# AQETHBluePill_w_RESET.net
KiCad netlist of a schematic drawn in EAGLE
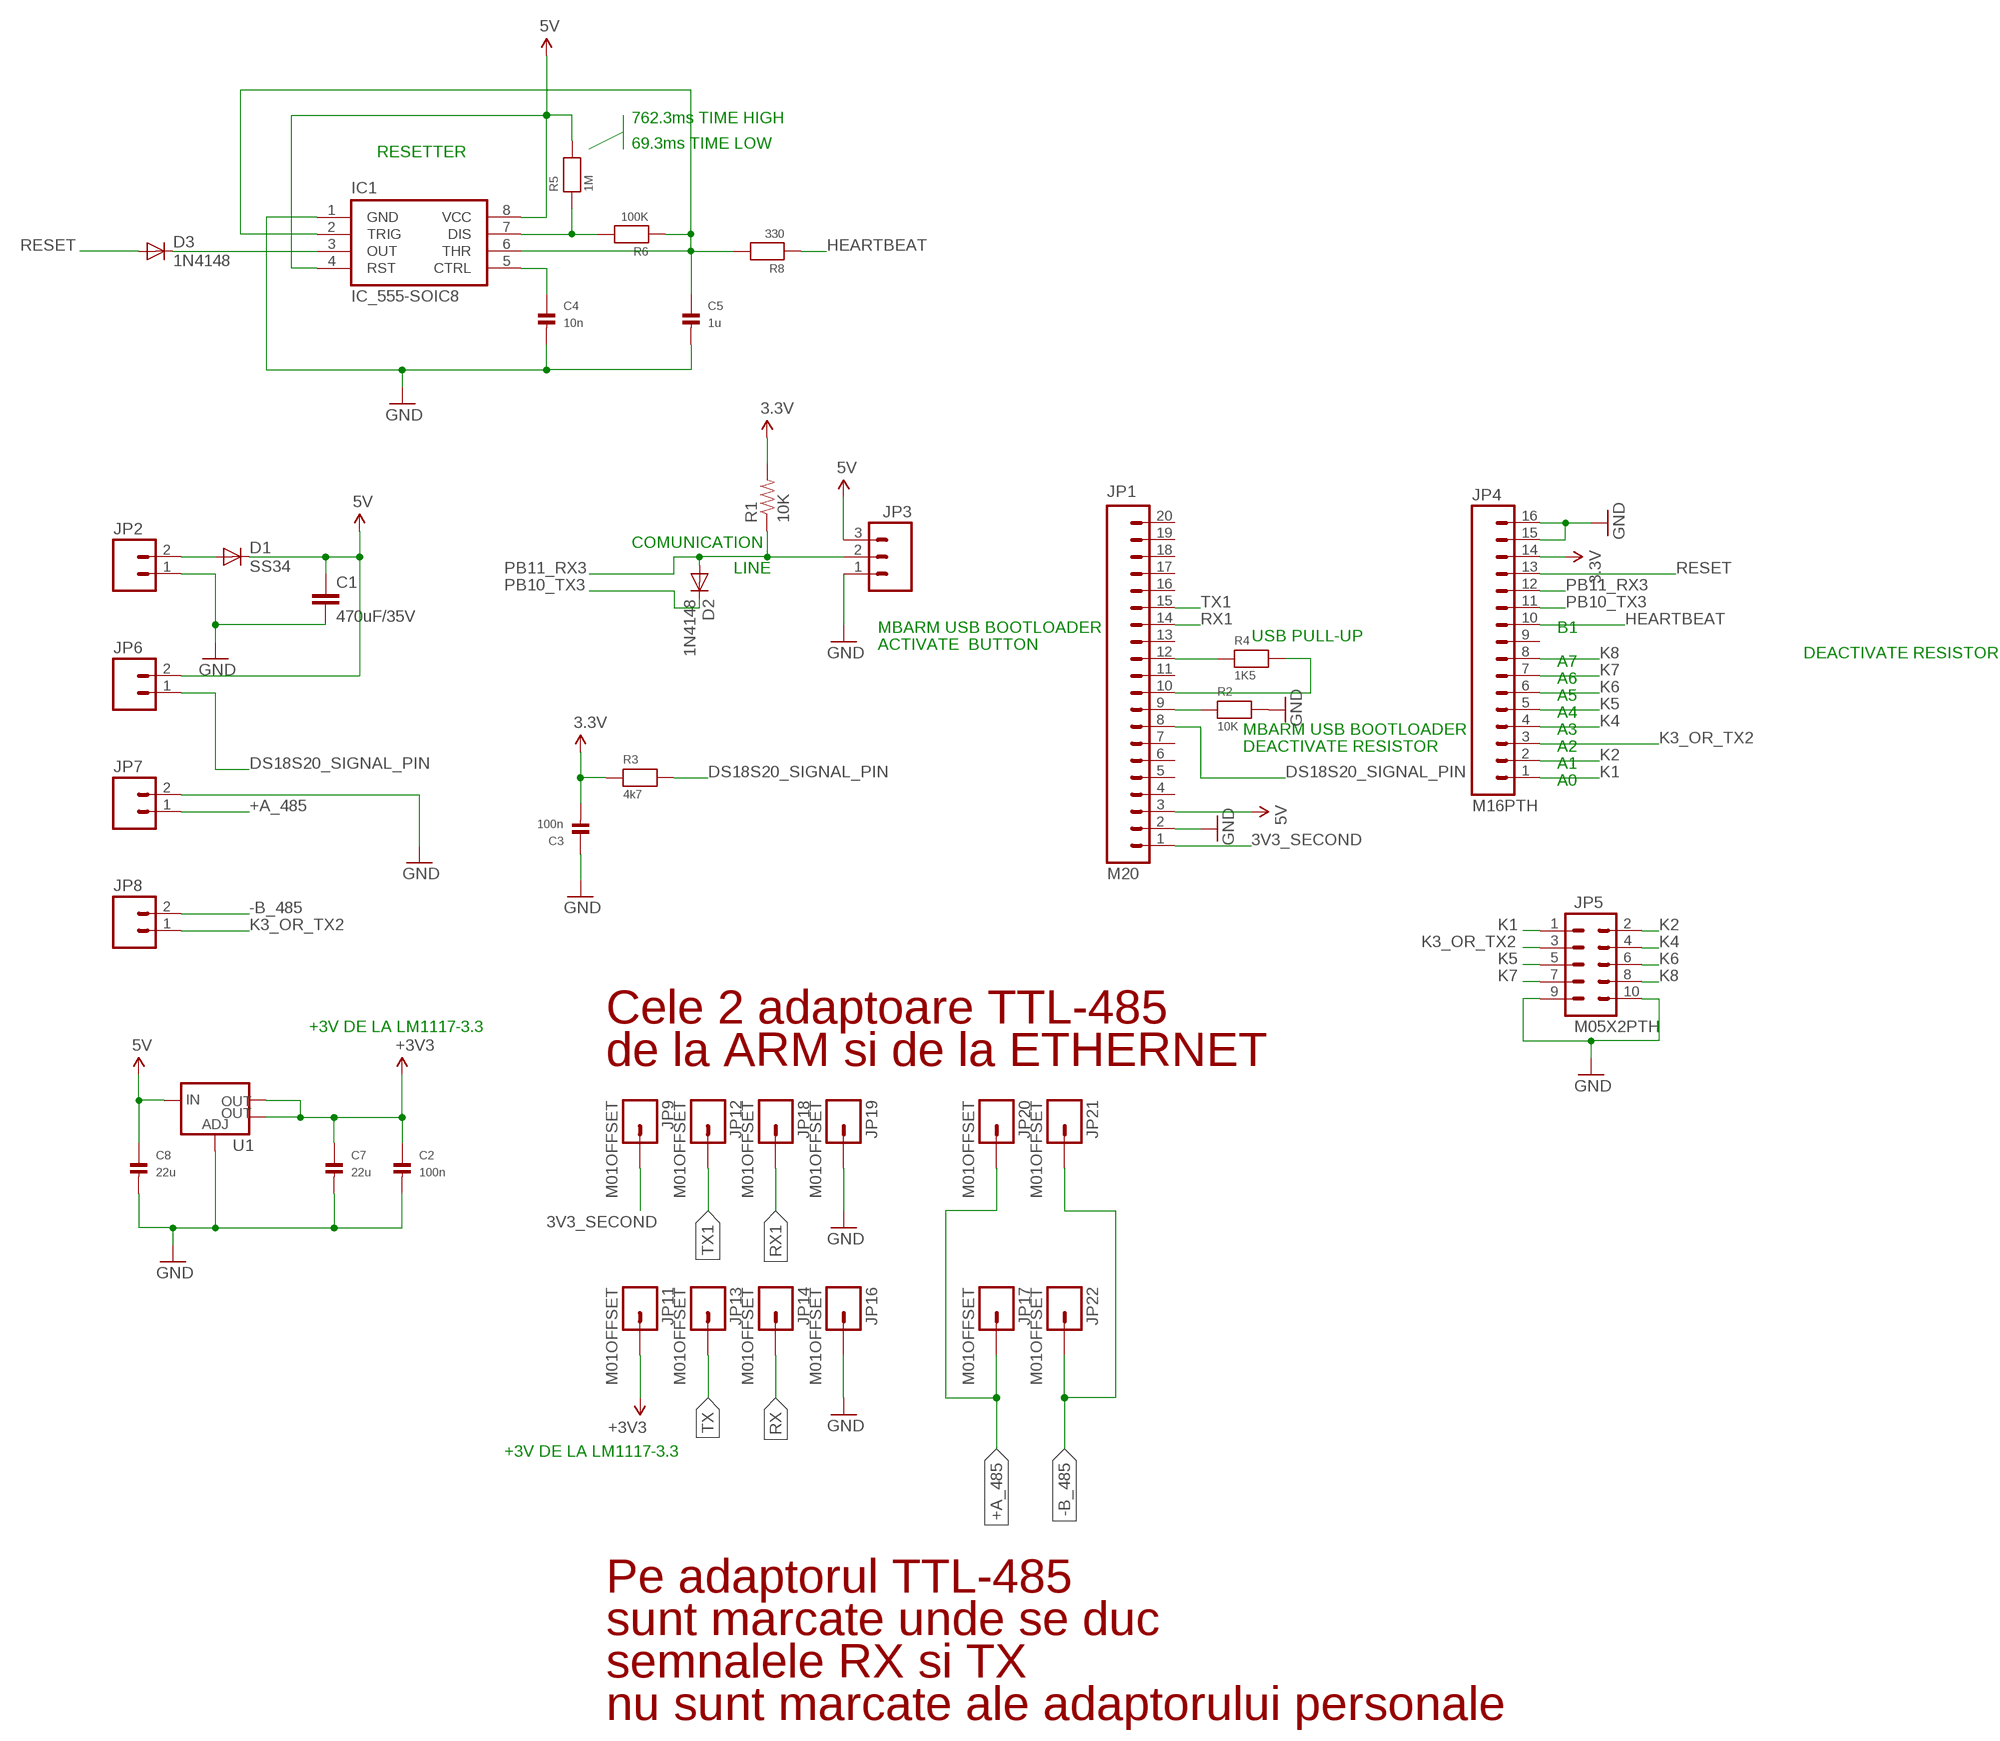
[diagram p0: schematic, sheet 1]

(export (version "E")
  (design (tool "Eeschema 10.0.6"))
  (components
    (comp (ref "C1")
      (value "470uF/35V")
      (footprint "eagle-import:CAP-PTH-5MM")
      (libsource (lib "eagle-import") (part "CAPPTH1"))
    )
    (comp (ref "C2")
      (value "100n")
      (footprint "eagle-import:_0805MP")
      (libsource (lib "eagle-import") (part "CAP_CERAMIC_0805MP"))
    )
    (comp (ref "C3")
      (value "100n")
      (footprint "eagle-import:_0805MP")
      (libsource (lib "eagle-import") (part "CAP_CERAMIC_0805MP"))
    )
    (comp (ref "C4")
      (value "10n")
      (footprint "eagle-import:_0805MP")
      (libsource (lib "eagle-import") (part "CAP_CERAMIC_0805MP"))
    )
    (comp (ref "C5")
      (value "1u")
      (footprint "eagle-import:1206")
      (libsource (lib "eagle-import") (part "CAP_CERAMIC1206"))
    )
    (comp (ref "C7")
      (value "22u")
      (footprint "eagle-import:1206")
      (libsource (lib "eagle-import") (part "CAP_CERAMIC1206"))
    )
    (comp (ref "C8")
      (value "22u")
      (footprint "eagle-import:1206")
      (libsource (lib "eagle-import") (part "CAP_CERAMIC1206"))
    )
    (comp (ref "D1")
      (value "SS34")
      (footprint "eagle-import:SMC")
      (libsource (lib "eagle-import") (part "DIODE-SMC"))
    )
    (comp (ref "D2")
      (value "1N4148")
      (footprint "eagle-import:MINIMELF")
      (libsource (lib "eagle-import") (part "DIODE-MINIMELF"))
    )
    (comp (ref "D3")
      (value "1N4148")
      (footprint "eagle-import:MINIMELF")
      (libsource (lib "eagle-import") (part "DIODE-MINIMELF"))
    )
    (comp (ref "IC1")
      (value "IC_555-SOIC8")
      (footprint "eagle-import:SOIC-8")
      (libsource (lib "eagle-import") (part "IC_555-SOIC8"))
    )
    (comp (ref "JP1")
      (value "M20")
      (footprint "eagle-import:1X20")
      (libsource (lib "eagle-import") (part "M20"))
    )
    (comp (ref "JP2")
      (value "M025MM")
      (footprint "eagle-import:SCREWTERMINAL-5MM-2")
      (libsource (lib "eagle-import") (part "M025MM"))
    )
    (comp (ref "JP3")
      (value "M03LOCK_LONGPADS")
      (footprint "eagle-import:1X03_LOCK_LONGPADS")
      (libsource (lib "eagle-import") (part "M03LOCK_LONGPADS"))
    )
    (comp (ref "JP4")
      (value "M16PTH")
      (footprint "eagle-import:1X16")
      (libsource (lib "eagle-import") (part "M16PTH"))
    )
    (comp (ref "JP5")
      (value "M05X2PTH")
      (footprint "eagle-import:AVR_ICSP")
      (libsource (lib "eagle-import") (part "M05X2PTH"))
    )
    (comp (ref "JP6")
      (value "M025MM")
      (footprint "eagle-import:SCREWTERMINAL-5MM-2")
      (libsource (lib "eagle-import") (part "M025MM"))
    )
    (comp (ref "JP7")
      (value "M025MM")
      (footprint "eagle-import:SCREWTERMINAL-5MM-2")
      (libsource (lib "eagle-import") (part "M025MM"))
    )
    (comp (ref "JP8")
      (value "M025MM")
      (footprint "eagle-import:SCREWTERMINAL-5MM-2")
      (libsource (lib "eagle-import") (part "M025MM"))
    )
    (comp (ref "JP9")
      (value "M01OFFSET")
      (footprint "eagle-import:1X01_OFFSET")
      (libsource (lib "eagle-import") (part "M01OFFSET"))
    )
    (comp (ref "JP11")
      (value "M01OFFSET")
      (footprint "eagle-import:1X01_OFFSET")
      (libsource (lib "eagle-import") (part "M01OFFSET"))
    )
    (comp (ref "JP12")
      (value "M01OFFSET")
      (footprint "eagle-import:1X01_OFFSET")
      (libsource (lib "eagle-import") (part "M01OFFSET"))
    )
    (comp (ref "JP13")
      (value "M01OFFSET")
      (footprint "eagle-import:1X01_OFFSET")
      (libsource (lib "eagle-import") (part "M01OFFSET"))
    )
    (comp (ref "JP14")
      (value "M01OFFSET")
      (footprint "eagle-import:1X01_OFFSET")
      (libsource (lib "eagle-import") (part "M01OFFSET"))
    )
    (comp (ref "JP16")
      (value "M01OFFSET")
      (footprint "eagle-import:1X01_OFFSET")
      (libsource (lib "eagle-import") (part "M01OFFSET"))
    )
    (comp (ref "JP17")
      (value "M01OFFSET")
      (footprint "eagle-import:1X01_OFFSET")
      (libsource (lib "eagle-import") (part "M01OFFSET"))
    )
    (comp (ref "JP18")
      (value "M01OFFSET")
      (footprint "eagle-import:1X01_OFFSET")
      (libsource (lib "eagle-import") (part "M01OFFSET"))
    )
    (comp (ref "JP19")
      (value "M01OFFSET")
      (footprint "eagle-import:1X01_OFFSET")
      (libsource (lib "eagle-import") (part "M01OFFSET"))
    )
    (comp (ref "JP20")
      (value "M01OFFSET")
      (footprint "eagle-import:1X01_OFFSET")
      (libsource (lib "eagle-import") (part "M01OFFSET"))
    )
    (comp (ref "JP21")
      (value "M01OFFSET")
      (footprint "eagle-import:1X01_OFFSET")
      (libsource (lib "eagle-import") (part "M01OFFSET"))
    )
    (comp (ref "JP22")
      (value "M01OFFSET")
      (footprint "eagle-import:1X01_OFFSET")
      (libsource (lib "eagle-import") (part "M01OFFSET"))
    )
    (comp (ref "R1")
      (value "10K")
      (footprint "eagle-import:1206")
      (libsource (lib "eagle-import") (part "RESISTOR1206"))
    )
    (comp (ref "R2")
      (value "10K")
      (footprint "eagle-import:_0805MP")
      (libsource (lib "eagle-import") (part "RESISTOR_0805MP"))
    )
    (comp (ref "R3")
      (value "4k7")
      (footprint "eagle-import:_0805MP")
      (libsource (lib "eagle-import") (part "RESISTOR_0805MP"))
    )
    (comp (ref "R4")
      (value "1K5")
      (footprint "eagle-import:_0805MP")
      (libsource (lib "eagle-import") (part "RESISTOR_0805MP"))
    )
    (comp (ref "R5")
      (value "1M")
      (footprint "eagle-import:_0805MP")
      (libsource (lib "eagle-import") (part "RESISTOR_0805MP"))
    )
    (comp (ref "R6")
      (value "100K")
      (footprint "eagle-import:_0805MP")
      (libsource (lib "eagle-import") (part "RESISTOR_0805MP"))
    )
    (comp (ref "R8")
      (value "330")
      (footprint "eagle-import:_0805MP")
      (libsource (lib "eagle-import") (part "RESISTOR_0805MP"))
    )
    (comp (ref "U1")
      (value "V_REG_LM1117SOT223")
      (footprint "eagle-import:SOT223")
      (libsource (lib "eagle-import") (part "V_REG_LM1117SOT223"))
    )
  )
  (nets
    (net (code "1") (name "+3V3") (class "Default")
      (node (ref "C2") (pin "1") (pinfunction "P$1_1") (pintype "passive"))
      (node (ref "C7") (pin "1") (pinfunction "P$1_1") (pintype "passive"))
      (node (ref "JP11") (pin "1") (pinfunction "1_1") (pintype "passive"))
      (node (ref "U1") (pin "2") (pinfunction "OUT_2") (pintype "output"))
      (node (ref "U1") (pin "4") (pinfunction "OUT_4") (pintype "output"))
    )
    (net (code "2") (name "+A_485") (class "Default")
      (node (ref "JP17") (pin "1") (pinfunction "1_1") (pintype "passive"))
      (node (ref "JP20") (pin "1") (pinfunction "1_1") (pintype "passive"))
      (node (ref "JP7") (pin "1") (pinfunction "1_1") (pintype "passive"))
    )
    (net (code "3") (name "-B_485") (class "Default")
      (node (ref "JP21") (pin "1") (pinfunction "1_1") (pintype "passive"))
      (node (ref "JP22") (pin "1") (pinfunction "1_1") (pintype "passive"))
      (node (ref "JP8") (pin "2") (pinfunction "2_2") (pintype "passive"))
    )
    (net (code "4") (name "/3V3_SECOND") (class "Default")
      (node (ref "JP1") (pin "1") (pinfunction "1_1") (pintype "passive"))
      (node (ref "JP9") (pin "1") (pinfunction "1_1") (pintype "passive"))
    )
    (net (code "5") (name "/DS18S20_SIGNAL_PIN") (class "Default")
      (node (ref "JP1") (pin "8") (pinfunction "8_8") (pintype "passive"))
      (node (ref "JP6") (pin "1") (pinfunction "1_1") (pintype "passive"))
      (node (ref "R3") (pin "2") (pinfunction "2_2") (pintype "passive"))
    )
    (net (code "6") (name "/HEARTBEAT") (class "Default")
      (node (ref "JP4") (pin "10") (pinfunction "10_10") (pintype "passive"))
      (node (ref "R8") (pin "1") (pinfunction "1_1") (pintype "passive"))
    )
    (net (code "7") (name "/K1") (class "Default")
      (node (ref "JP4") (pin "1") (pinfunction "1_1") (pintype "passive"))
      (node (ref "JP5") (pin "1") (pinfunction "1_1") (pintype "passive"))
    )
    (net (code "8") (name "/K2") (class "Default")
      (node (ref "JP4") (pin "2") (pinfunction "2_2") (pintype "passive"))
      (node (ref "JP5") (pin "2") (pinfunction "2_2") (pintype "passive"))
    )
    (net (code "9") (name "/K3_OR_TX2") (class "Default")
      (node (ref "JP4") (pin "3") (pinfunction "3_3") (pintype "passive"))
      (node (ref "JP5") (pin "3") (pinfunction "3_3") (pintype "passive"))
      (node (ref "JP8") (pin "1") (pinfunction "1_1") (pintype "passive"))
    )
    (net (code "10") (name "/K4") (class "Default")
      (node (ref "JP4") (pin "4") (pinfunction "4_4") (pintype "passive"))
      (node (ref "JP5") (pin "4") (pinfunction "4_4") (pintype "passive"))
    )
    (net (code "11") (name "/K5") (class "Default")
      (node (ref "JP4") (pin "5") (pinfunction "5_5") (pintype "passive"))
      (node (ref "JP5") (pin "5") (pinfunction "5_5") (pintype "passive"))
    )
    (net (code "12") (name "/K6") (class "Default")
      (node (ref "JP4") (pin "6") (pinfunction "6_6") (pintype "passive"))
      (node (ref "JP5") (pin "6") (pinfunction "6_6") (pintype "passive"))
    )
    (net (code "13") (name "/K7") (class "Default")
      (node (ref "JP4") (pin "7") (pinfunction "7_7") (pintype "passive"))
      (node (ref "JP5") (pin "7") (pinfunction "7_7") (pintype "passive"))
    )
    (net (code "14") (name "/K8") (class "Default")
      (node (ref "JP4") (pin "8") (pinfunction "8_8") (pintype "passive"))
      (node (ref "JP5") (pin "8") (pinfunction "8_8") (pintype "passive"))
    )
    (net (code "15") (name "/PB10_TX3") (class "Default")
      (node (ref "D2") (pin "C") (pinfunction "C_C") (pintype "passive"))
      (node (ref "JP4") (pin "11") (pinfunction "11_11") (pintype "passive"))
    )
    (net (code "16") (name "/PB11_RX3") (class "Default")
      (node (ref "D2") (pin "A") (pinfunction "A_A") (pintype "passive"))
      (node (ref "JP3") (pin "2") (pinfunction "2_2") (pintype "passive"))
      (node (ref "JP4") (pin "12") (pinfunction "12_12") (pintype "passive"))
      (node (ref "R1") (pin "1") (pinfunction "1_1") (pintype "passive"))
    )
    (net (code "17") (name "/RESET") (class "Default")
      (node (ref "D3") (pin "A") (pinfunction "A_A") (pintype "passive"))
      (node (ref "JP4") (pin "13") (pinfunction "13_13") (pintype "passive"))
    )
    (net (code "18") (name "3.3V") (class "Default")
      (node (ref "C3") (pin "2") (pinfunction "P$2_2") (pintype "passive"))
      (node (ref "JP4") (pin "14") (pinfunction "14_14") (pintype "passive"))
      (node (ref "R1") (pin "2") (pinfunction "2_2") (pintype "passive"))
      (node (ref "R3") (pin "1") (pinfunction "1_1") (pintype "passive"))
    )
    (net (code "19") (name "5V") (class "Default")
      (node (ref "C1") (pin "1") (pinfunction "1_1") (pintype "passive"))
      (node (ref "C8") (pin "1") (pinfunction "P$1_1") (pintype "passive"))
      (node (ref "D1") (pin "C") (pinfunction "C_C") (pintype "passive"))
      (node (ref "IC1") (pin "4") (pinfunction "RST_4") (pintype "input"))
      (node (ref "IC1") (pin "8") (pinfunction "VCC_8") (pintype "power_in"))
      (node (ref "JP1") (pin "3") (pinfunction "3_3") (pintype "passive"))
      (node (ref "JP3") (pin "3") (pinfunction "3_3") (pintype "passive"))
      (node (ref "JP6") (pin "2") (pinfunction "2_2") (pintype "passive"))
      (node (ref "R5") (pin "2") (pinfunction "2_2") (pintype "passive"))
      (node (ref "U1") (pin "3") (pinfunction "IN_3") (pintype "input"))
    )
    (net (code "20") (name "GND") (class "Default")
      (node (ref "C1") (pin "2") (pinfunction "2_2") (pintype "passive"))
      (node (ref "C2") (pin "2") (pinfunction "P$2_2") (pintype "passive"))
      (node (ref "C3") (pin "1") (pinfunction "P$1_1") (pintype "passive"))
      (node (ref "C4") (pin "2") (pinfunction "P$2_2") (pintype "passive"))
      (node (ref "C5") (pin "2") (pinfunction "P$2_2") (pintype "passive"))
      (node (ref "C7") (pin "2") (pinfunction "P$2_2") (pintype "passive"))
      (node (ref "C8") (pin "2") (pinfunction "P$2_2") (pintype "passive"))
      (node (ref "IC1") (pin "1") (pinfunction "GND_1") (pintype "power_in"))
      (node (ref "JP1") (pin "2") (pinfunction "2_2") (pintype "passive"))
      (node (ref "JP16") (pin "1") (pinfunction "1_1") (pintype "passive"))
      (node (ref "JP19") (pin "1") (pinfunction "1_1") (pintype "passive"))
      (node (ref "JP2") (pin "1") (pinfunction "1_1") (pintype "passive"))
      (node (ref "JP3") (pin "1") (pinfunction "1_1") (pintype "passive"))
      (node (ref "JP4") (pin "15") (pinfunction "15_15") (pintype "passive"))
      (node (ref "JP4") (pin "16") (pinfunction "16_16") (pintype "passive"))
      (node (ref "JP5") (pin "10") (pinfunction "10_10") (pintype "passive"))
      (node (ref "JP5") (pin "9") (pinfunction "9_9") (pintype "passive"))
      (node (ref "JP7") (pin "2") (pinfunction "2_2") (pintype "passive"))
      (node (ref "R2") (pin "2") (pinfunction "2_2") (pintype "passive"))
      (node (ref "U1") (pin "1") (pinfunction "ADJ_1") (pintype "input"))
    )
    (net (code "21") (name "Net-(C4-P$1)") (class "Default")
      (node (ref "C4") (pin "1") (pinfunction "P$1_1") (pintype "passive"))
      (node (ref "IC1") (pin "5") (pinfunction "CTRL_5") (pintype "power_in"))
    )
    (net (code "22") (name "Net-(C5-P$1)") (class "Default")
      (node (ref "C5") (pin "1") (pinfunction "P$1_1") (pintype "passive"))
      (node (ref "IC1") (pin "2") (pinfunction "TRIG_2") (pintype "input"))
      (node (ref "IC1") (pin "6") (pinfunction "THR_6") (pintype "input"))
      (node (ref "R6") (pin "1") (pinfunction "1_1") (pintype "passive"))
      (node (ref "R8") (pin "2") (pinfunction "2_2") (pintype "passive"))
    )
    (net (code "23") (name "Net-(D1-PadA)") (class "Default")
      (node (ref "D1") (pin "A") (pinfunction "A_A") (pintype "passive"))
      (node (ref "JP2") (pin "2") (pinfunction "2_2") (pintype "passive"))
    )
    (net (code "24") (name "Net-(IC1-DIS)") (class "Default")
      (node (ref "IC1") (pin "7") (pinfunction "DIS_7") (pintype "input"))
      (node (ref "R5") (pin "1") (pinfunction "1_1") (pintype "passive"))
      (node (ref "R6") (pin "2") (pinfunction "2_2") (pintype "passive"))
    )
    (net (code "25") (name "Net-(IC1-OUT)") (class "Default")
      (node (ref "D3") (pin "C") (pinfunction "C_C") (pintype "passive"))
      (node (ref "IC1") (pin "3") (pinfunction "OUT_3") (pintype "output"))
    )
    (net (code "26") (name "Net-(JP1-Pad9)") (class "Default")
      (node (ref "JP1") (pin "9") (pinfunction "9_9") (pintype "passive"))
      (node (ref "R2") (pin "1") (pinfunction "1_1") (pintype "passive"))
    )
    (net (code "27") (name "Net-(JP1-Pad10)") (class "Default")
      (node (ref "JP1") (pin "10") (pinfunction "10_10") (pintype "passive"))
      (node (ref "R4") (pin "2") (pinfunction "2_2") (pintype "passive"))
    )
    (net (code "28") (name "Net-(JP1-Pad12)") (class "Default")
      (node (ref "JP1") (pin "12") (pinfunction "12_12") (pintype "passive"))
      (node (ref "R4") (pin "1") (pinfunction "1_1") (pintype "passive"))
    )
    (net (code "29") (name "RX") (class "Default")
      (node (ref "JP14") (pin "1") (pinfunction "1_1") (pintype "passive"))
    )
    (net (code "30") (name "RX1") (class "Default")
      (node (ref "JP1") (pin "14") (pinfunction "14_14") (pintype "passive"))
      (node (ref "JP18") (pin "1") (pinfunction "1_1") (pintype "passive"))
    )
    (net (code "31") (name "TX") (class "Default")
      (node (ref "JP13") (pin "1") (pinfunction "1_1") (pintype "passive"))
    )
    (net (code "32") (name "TX1") (class "Default")
      (node (ref "JP1") (pin "15") (pinfunction "15_15") (pintype "passive"))
      (node (ref "JP12") (pin "1") (pinfunction "1_1") (pintype "passive"))
    )
    (net (code "33") (name "unconnected-(JP1-Pad4)") (class "Default")
      (node (ref "JP1") (pin "4") (pinfunction "4_4") (pintype "passive"))
    )
    (net (code "34") (name "unconnected-(JP1-Pad5)") (class "Default")
      (node (ref "JP1") (pin "5") (pinfunction "5_5") (pintype "passive"))
    )
    (net (code "35") (name "unconnected-(JP1-Pad6)") (class "Default")
      (node (ref "JP1") (pin "6") (pinfunction "6_6") (pintype "passive"))
    )
    (net (code "36") (name "unconnected-(JP1-Pad7)") (class "Default")
      (node (ref "JP1") (pin "7") (pinfunction "7_7") (pintype "passive"))
    )
    (net (code "37") (name "unconnected-(JP1-Pad11)") (class "Default")
      (node (ref "JP1") (pin "11") (pinfunction "11_11") (pintype "passive"))
    )
    (net (code "38") (name "unconnected-(JP1-Pad13)") (class "Default")
      (node (ref "JP1") (pin "13") (pinfunction "13_13") (pintype "passive"))
    )
    (net (code "39") (name "unconnected-(JP1-Pad16)") (class "Default")
      (node (ref "JP1") (pin "16") (pinfunction "16_16") (pintype "passive"))
    )
    (net (code "40") (name "unconnected-(JP1-Pad17)") (class "Default")
      (node (ref "JP1") (pin "17") (pinfunction "17_17") (pintype "passive"))
    )
    (net (code "41") (name "unconnected-(JP1-Pad18)") (class "Default")
      (node (ref "JP1") (pin "18") (pinfunction "18_18") (pintype "passive"))
    )
    (net (code "42") (name "unconnected-(JP1-Pad19)") (class "Default")
      (node (ref "JP1") (pin "19") (pinfunction "19_19") (pintype "passive"))
    )
    (net (code "43") (name "unconnected-(JP1-Pad20)") (class "Default")
      (node (ref "JP1") (pin "20") (pinfunction "20_20") (pintype "passive"))
    )
    (net (code "44") (name "unconnected-(JP4-Pad9)") (class "Default")
      (node (ref "JP4") (pin "9") (pinfunction "9_9") (pintype "passive"))
    )
  )
)
